# main.net
KiCad netlist of a schematic drawn in Altium Designer
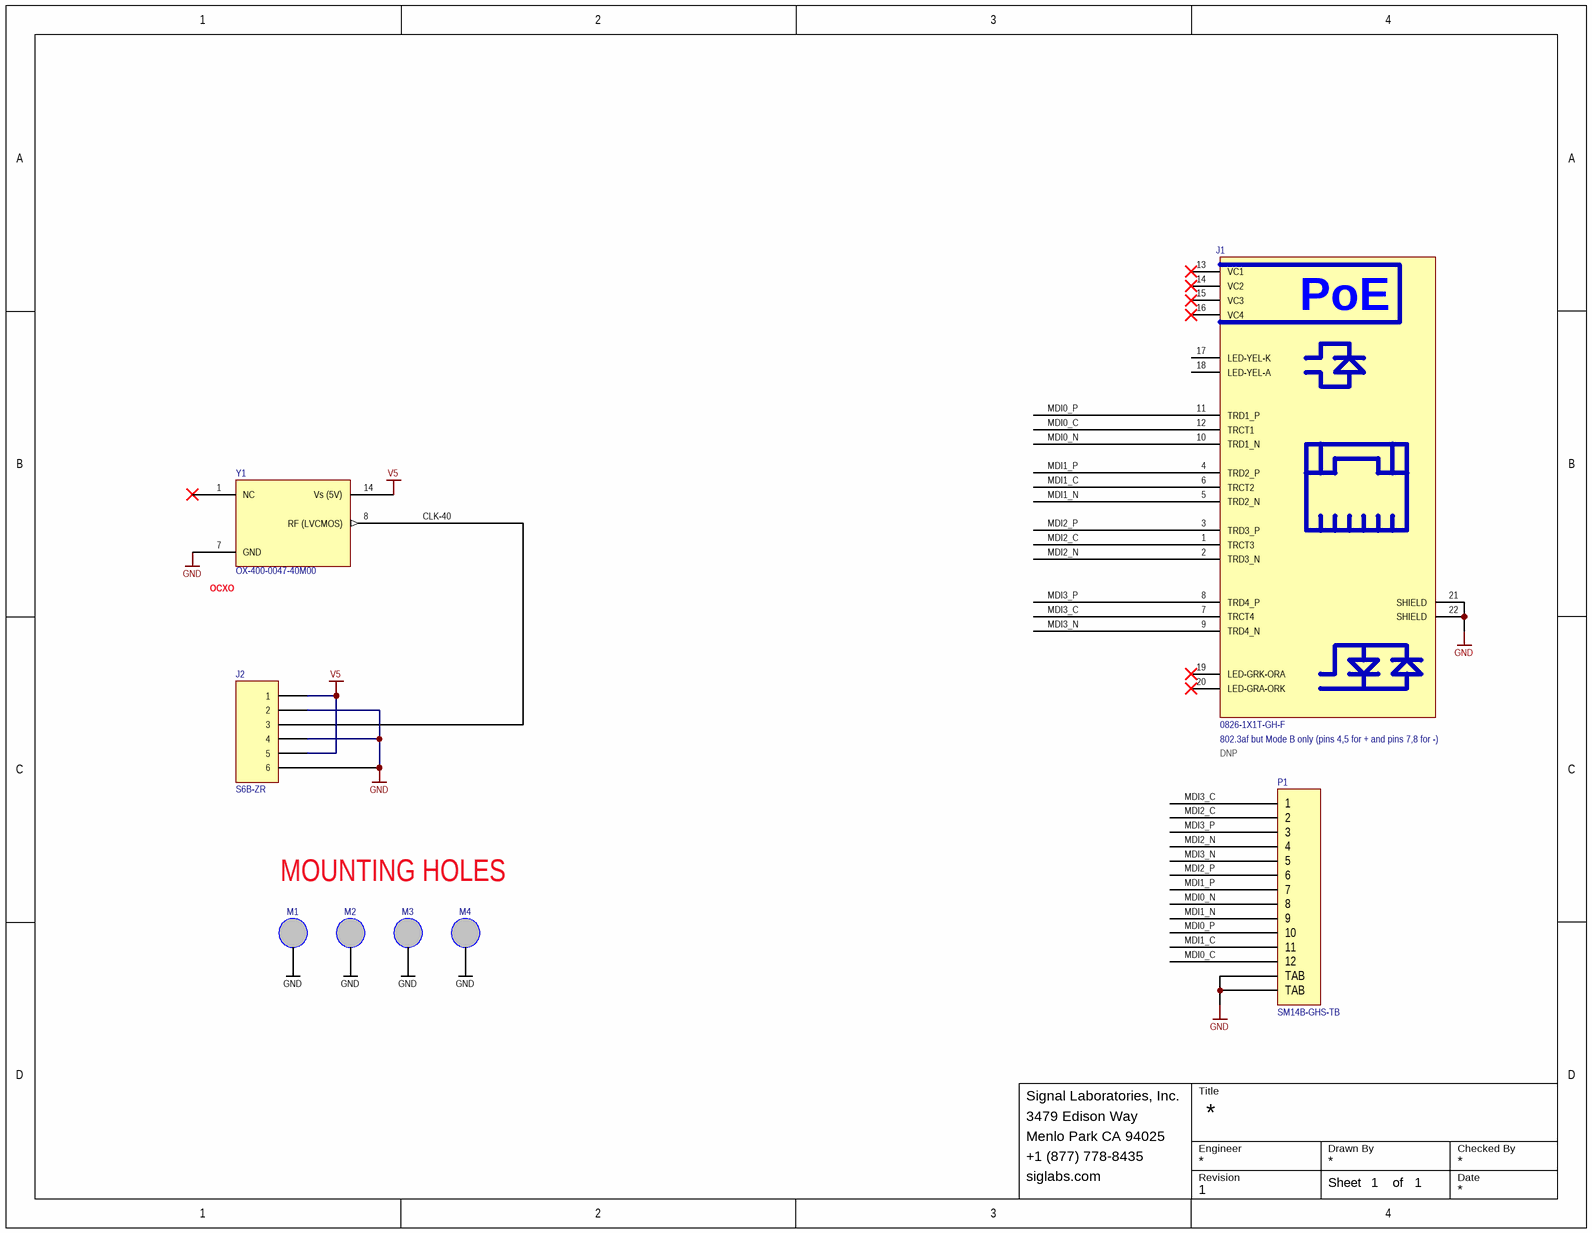
[diagram p0: main.SchDoc]

(export (version "E")
  (design (tool "Eeschema 10.0.6"))
  (components
    (comp (ref "J1")
      (value "0826-1X1T-GH-F")
      (footprint "0826")
      (description "Gigabit Ethernet 35W PoE MAGJACK")
      (fields (field (name "MANUFACTURER") "Bel-Fuse") (field (name "DO NOT PLACE") "DNP"))
      (libsource (lib "bel-fuse") (part "0826-1X1T-GH-F"))
    )
    (comp (ref "J2")
      (value "S6B-ZR")
      (footprint "jst:S6B-ZR")
      (description "1.5mm pitch right angle 6-position")
      (fields (field (name "MANUFACTURER") "JST"))
      (libsource (lib "jst") (part "S6B-ZR"))
    )
    (comp (ref "M1") (value "MOUNT350") (footprint "mount350") (libsource (lib "Misc") (part "M3_HOLE")))
    (comp (ref "M2") (value "MOUNT350") (footprint "mount350") (libsource (lib "Misc") (part "M3_HOLE")))
    (comp (ref "M3") (value "MOUNT350") (footprint "mount350") (libsource (lib "Misc") (part "M3_HOLE")))
    (comp (ref "M4") (value "MOUNT350") (footprint "mount350") (libsource (lib "Misc") (part "M3_HOLE")))
    (comp (ref "P1")
      (value "SM14B-GHS-TB")
      (footprint "jst:SM12B-GHS-TBT")
      (description "Right Entry Shrouded Connector; 12-position")
      (fields (field (name "MANUFACTURER") "JST"))
      (libsource (lib "jst") (part "BM12B-GHS-TBT"))
    )
    (comp (ref "Y1")
      (value "OX-400-0047-40M00")
      (footprint "G125")
      (description "Oven Controlled Precision Oscillator, 10MHz")
      (fields (field (name "MANUFACTURER") "Vectron"))
      (libsource (lib "vectron") (part "OX-400-0047-40M00"))
    )
  )
  (nets
    (net (code "1") (name "/CLK-40") (class "Default")
      (node (ref "J2") (pin "3") (pinfunction "3_3") (pintype "passive"))
      (node (ref "Y1") (pin "8") (pinfunction "RF_(LVCMOS)_8") (pintype "output"))
    )
    (net (code "2") (name "/MDI0_C") (class "Default")
      (node (ref "J1") (pin "12") (pinfunction "TRCT1_12") (pintype "passive"))
      (node (ref "P1") (pin "12") (pinfunction "12_12") (pintype "passive"))
    )
    (net (code "3") (name "/MDI0_N") (class "Default")
      (node (ref "J1") (pin "10") (pinfunction "TRD1_N_10") (pintype "passive"))
      (node (ref "P1") (pin "8") (pinfunction "8_8") (pintype "passive"))
    )
    (net (code "4") (name "/MDI0_P") (class "Default")
      (node (ref "J1") (pin "11") (pinfunction "TRD1_P_11") (pintype "passive"))
      (node (ref "P1") (pin "10") (pinfunction "10_10") (pintype "passive"))
    )
    (net (code "5") (name "/MDI1_C") (class "Default")
      (node (ref "J1") (pin "6") (pinfunction "TRCT2_6") (pintype "passive"))
      (node (ref "P1") (pin "11") (pinfunction "11_11") (pintype "passive"))
    )
    (net (code "6") (name "/MDI1_N") (class "Default")
      (node (ref "J1") (pin "5") (pinfunction "TRD2_N_5") (pintype "passive"))
      (node (ref "P1") (pin "9") (pinfunction "9_9") (pintype "passive"))
    )
    (net (code "7") (name "/MDI1_P") (class "Default")
      (node (ref "J1") (pin "4") (pinfunction "TRD2_P_4") (pintype "passive"))
      (node (ref "P1") (pin "7") (pinfunction "7_7") (pintype "passive"))
    )
    (net (code "8") (name "/MDI2_C") (class "Default")
      (node (ref "J1") (pin "1") (pinfunction "TRCT3_1") (pintype "passive"))
      (node (ref "P1") (pin "2") (pinfunction "2_2") (pintype "passive"))
    )
    (net (code "9") (name "/MDI2_N") (class "Default")
      (node (ref "J1") (pin "2") (pinfunction "TRD3_N_2") (pintype "passive"))
      (node (ref "P1") (pin "4") (pinfunction "4_4") (pintype "passive"))
    )
    (net (code "10") (name "/MDI2_P") (class "Default")
      (node (ref "J1") (pin "3") (pinfunction "TRD3_P_3") (pintype "passive"))
      (node (ref "P1") (pin "6") (pinfunction "6_6") (pintype "passive"))
    )
    (net (code "11") (name "/MDI3_C") (class "Default")
      (node (ref "J1") (pin "7") (pinfunction "TRCT4_7") (pintype "passive"))
      (node (ref "P1") (pin "1") (pinfunction "1_1") (pintype "passive"))
    )
    (net (code "12") (name "/MDI3_N") (class "Default")
      (node (ref "J1") (pin "9") (pinfunction "TRD4_N_9") (pintype "passive"))
      (node (ref "P1") (pin "5") (pinfunction "5_5") (pintype "passive"))
    )
    (net (code "13") (name "/MDI3_P") (class "Default")
      (node (ref "J1") (pin "8") (pinfunction "TRD4_P_8") (pintype "passive"))
      (node (ref "P1") (pin "3") (pinfunction "3_3") (pintype "passive"))
    )
    (net (code "14") (name "GND") (class "Default")
      (node (ref "J1") (pin "21") (pinfunction "SHIELD_21") (pintype "passive"))
      (node (ref "J1") (pin "22") (pinfunction "SHIELD_22") (pintype "passive"))
      (node (ref "J2") (pin "2") (pinfunction "2_2") (pintype "passive"))
      (node (ref "J2") (pin "4") (pinfunction "4_4") (pintype "passive"))
      (node (ref "J2") (pin "6") (pinfunction "6_6") (pintype "passive"))
      (node (ref "M1") (pin "1") (pinfunction "GND_1") (pintype "power_in"))
      (node (ref "M2") (pin "1") (pinfunction "GND_1") (pintype "power_in"))
      (node (ref "M3") (pin "1") (pinfunction "GND_1") (pintype "power_in"))
      (node (ref "M4") (pin "1") (pinfunction "GND_1") (pintype "power_in"))
      (node (ref "P1") (pin "13") (pinfunction "TAB_13") (pintype "passive"))
      (node (ref "P1") (pin "14") (pinfunction "TAB_14") (pintype "passive"))
      (node (ref "Y1") (pin "7") (pinfunction "GND_7") (pintype "power_in"))
    )
    (net (code "15") (name "V5") (class "Default")
      (node (ref "J2") (pin "1") (pinfunction "1_1") (pintype "passive"))
      (node (ref "J2") (pin "5") (pinfunction "5_5") (pintype "passive"))
      (node (ref "Y1") (pin "14") (pinfunction "Vs_(5V)_14") (pintype "power_in"))
    )
    (net (code "16") (name "unconnected-(J1-LED-GRA-ORK-Pad20)") (class "Default")
      (node (ref "J1") (pin "20") (pinfunction "LED-GRA-ORK_20") (pintype "passive+no_connect"))
    )
    (net (code "17") (name "unconnected-(J1-LED-GRK-ORA-Pad19)") (class "Default")
      (node (ref "J1") (pin "19") (pinfunction "LED-GRK-ORA_19") (pintype "passive+no_connect"))
    )
    (net (code "18") (name "unconnected-(J1-LED-YEL-A-Pad18)") (class "Default")
      (node (ref "J1") (pin "18") (pinfunction "LED-YEL-A_18") (pintype "passive"))
    )
    (net (code "19") (name "unconnected-(J1-LED-YEL-K-Pad17)") (class "Default")
      (node (ref "J1") (pin "17") (pinfunction "LED-YEL-K_17") (pintype "passive"))
    )
    (net (code "20") (name "unconnected-(J1-VC1-Pad13)") (class "Default")
      (node (ref "J1") (pin "13") (pinfunction "VC1_13") (pintype "passive+no_connect"))
    )
    (net (code "21") (name "unconnected-(J1-VC2-Pad14)") (class "Default")
      (node (ref "J1") (pin "14") (pinfunction "VC2_14") (pintype "passive+no_connect"))
    )
    (net (code "22") (name "unconnected-(J1-VC3-Pad15)") (class "Default")
      (node (ref "J1") (pin "15") (pinfunction "VC3_15") (pintype "passive+no_connect"))
    )
    (net (code "23") (name "unconnected-(J1-VC4-Pad16)") (class "Default")
      (node (ref "J1") (pin "16") (pinfunction "VC4_16") (pintype "passive+no_connect"))
    )
    (net (code "24") (name "unconnected-(Y1-NC-Pad1)") (class "Default")
      (node (ref "Y1") (pin "1") (pinfunction "NC_1") (pintype "passive+no_connect"))
    )
  )
)
